# 7_Segment_Display_Peripheral.net
KiCad netlist of a schematic drawn in EAGLE
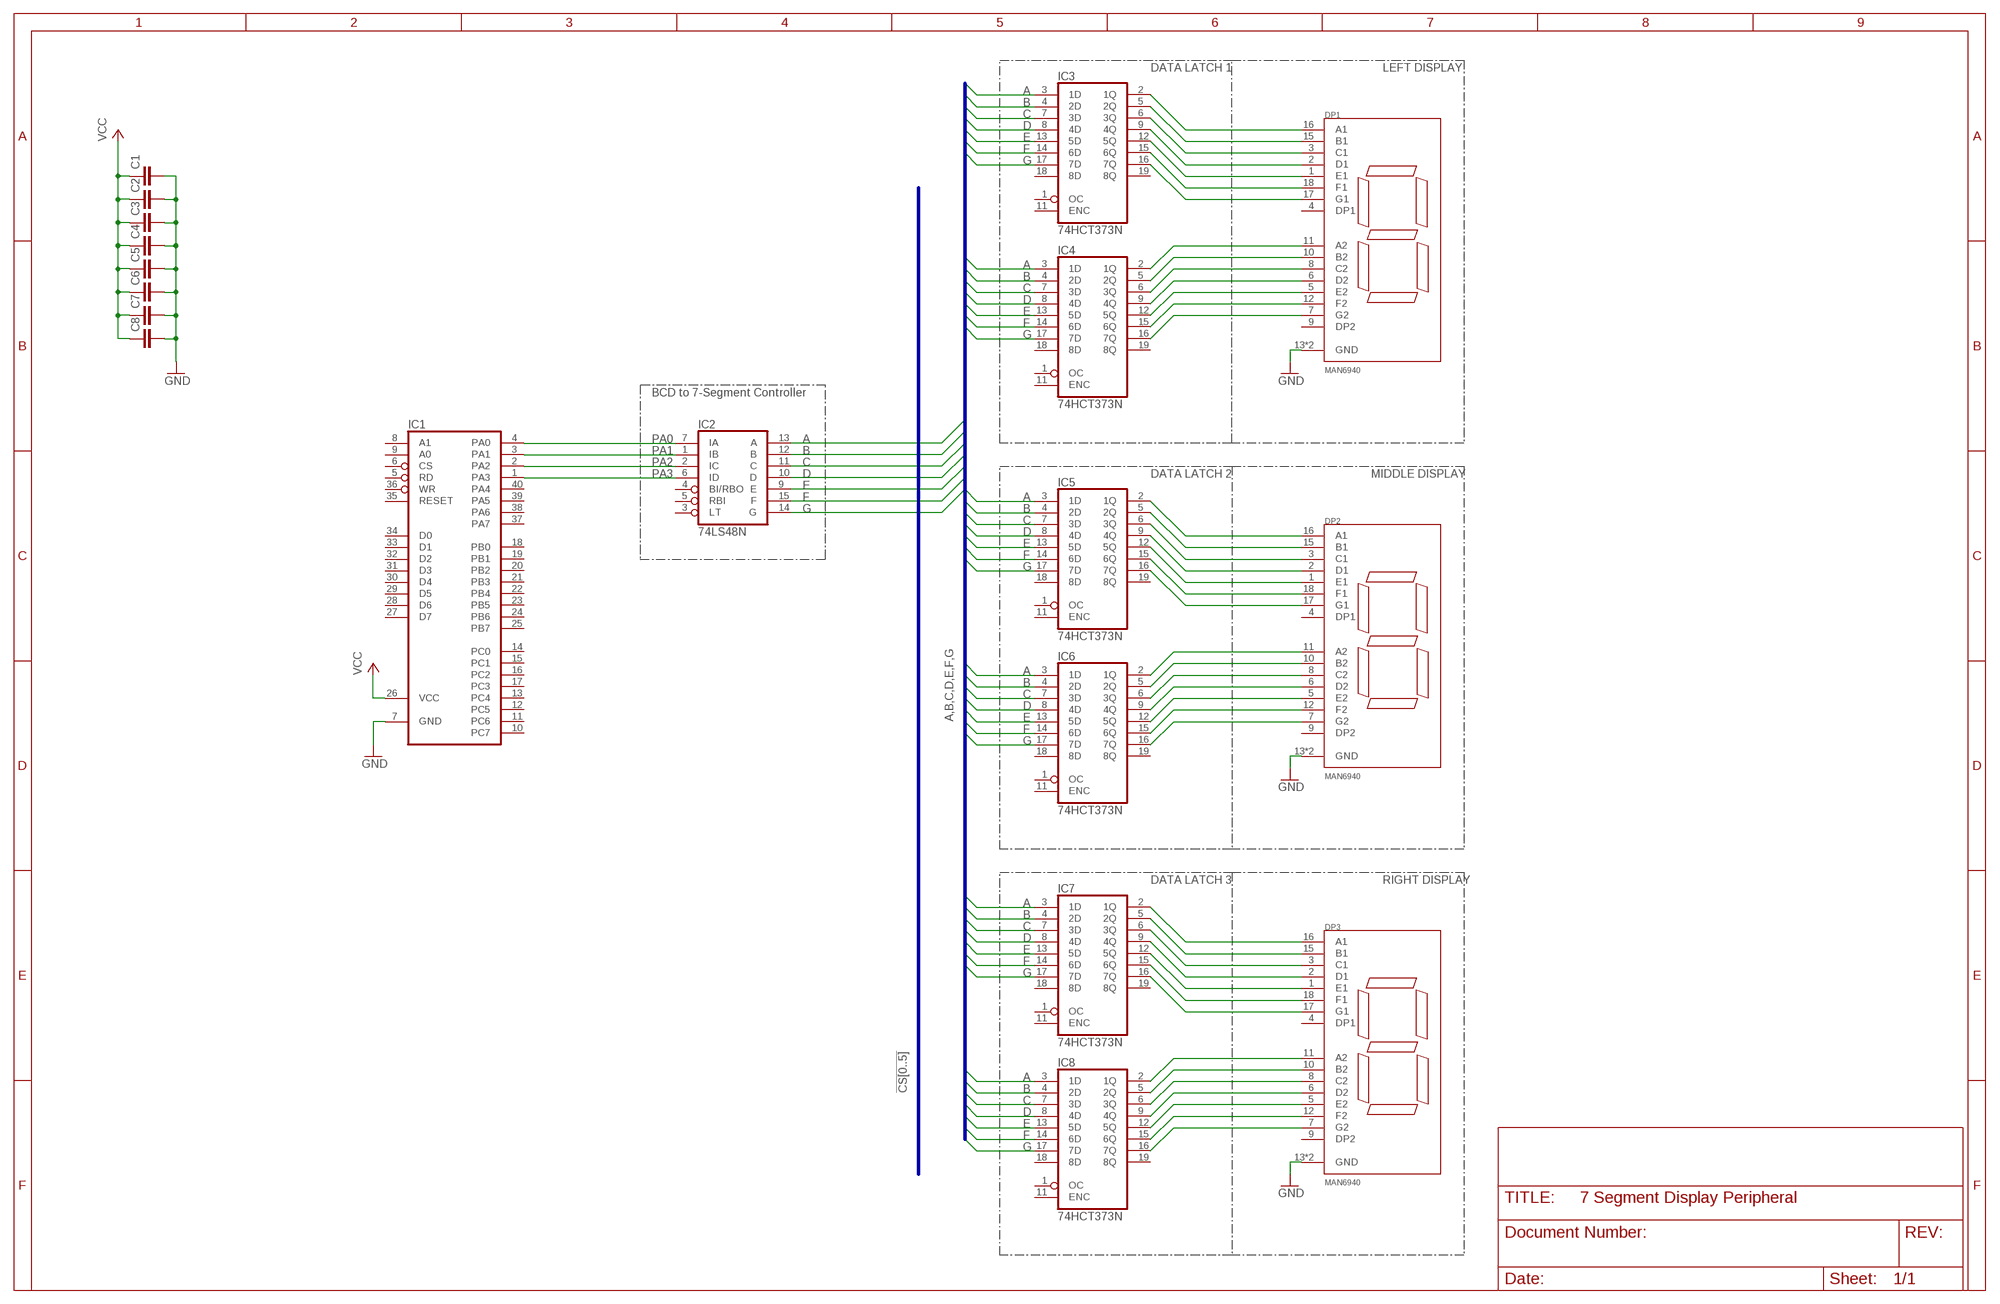
[diagram p0: schematic, sheet 1]

(export (version "E")
  (design (tool "Eeschema 10.0.6"))
  (components
    (comp (ref "C1")
      (value "C-EU050-024X044")
      (footprint "eagle-import:C050-024X044")
      (libsource (lib "eagle-import") (part "C-EU050-024X044"))
    )
    (comp (ref "C2")
      (value "C-EU050-024X044")
      (footprint "eagle-import:C050-024X044")
      (libsource (lib "eagle-import") (part "C-EU050-024X044"))
    )
    (comp (ref "C3")
      (value "C-EU050-024X044")
      (footprint "eagle-import:C050-024X044")
      (libsource (lib "eagle-import") (part "C-EU050-024X044"))
    )
    (comp (ref "C4")
      (value "C-EU050-024X044")
      (footprint "eagle-import:C050-024X044")
      (libsource (lib "eagle-import") (part "C-EU050-024X044"))
    )
    (comp (ref "C5")
      (value "C-EU050-024X044")
      (footprint "eagle-import:C050-024X044")
      (libsource (lib "eagle-import") (part "C-EU050-024X044"))
    )
    (comp (ref "C6")
      (value "C-EU050-024X044")
      (footprint "eagle-import:C050-024X044")
      (libsource (lib "eagle-import") (part "C-EU050-024X044"))
    )
    (comp (ref "C7")
      (value "C-EU050-024X044")
      (footprint "eagle-import:C050-024X044")
      (libsource (lib "eagle-import") (part "C-EU050-024X044"))
    )
    (comp (ref "C8")
      (value "C-EU050-024X044")
      (footprint "eagle-import:C050-024X044")
      (libsource (lib "eagle-import") (part "C-EU050-024X044"))
    )
    (comp (ref "DP1")
      (value "MAN6940")
      (footprint "eagle-import:MAN6940")
      (libsource (lib "eagle-import") (part "MAN6940"))
    )
    (comp (ref "DP2")
      (value "MAN6940")
      (footprint "eagle-import:MAN6940")
      (libsource (lib "eagle-import") (part "MAN6940"))
    )
    (comp (ref "DP3")
      (value "MAN6940")
      (footprint "eagle-import:MAN6940")
      (libsource (lib "eagle-import") (part "MAN6940"))
    )
    (comp (ref "IC1")
      (value "82C55A")
      (footprint "eagle-import:DIL40")
      (fields (field (name "MF") "INTERSIL") (field (name "MPN") "IP82C55AZ"))
      (libsource (lib "eagle-import") (part "82C55A"))
    )
    (comp (ref "IC2")
      (value "74LS48N")
      (footprint "eagle-import:DIL16")
      (libsource (lib "eagle-import") (part "7448NLS"))
    )
    (comp (ref "IC3")
      (value "74HCT373N")
      (footprint "eagle-import:DIL20")
      (libsource (lib "eagle-import") (part "74373NHCT"))
    )
    (comp (ref "IC4")
      (value "74HCT373N")
      (footprint "eagle-import:DIL20")
      (libsource (lib "eagle-import") (part "74373NHCT"))
    )
    (comp (ref "IC5")
      (value "74HCT373N")
      (footprint "eagle-import:DIL20")
      (libsource (lib "eagle-import") (part "74373NHCT"))
    )
    (comp (ref "IC6")
      (value "74HCT373N")
      (footprint "eagle-import:DIL20")
      (libsource (lib "eagle-import") (part "74373NHCT"))
    )
    (comp (ref "IC7")
      (value "74HCT373N")
      (footprint "eagle-import:DIL20")
      (libsource (lib "eagle-import") (part "74373NHCT"))
    )
    (comp (ref "IC8")
      (value "74HCT373N")
      (footprint "eagle-import:DIL20")
      (libsource (lib "eagle-import") (part "74373NHCT"))
    )
  )
  (nets
    (net (code "7") (name "/A") (class "Default")
      (node (ref "IC2") (pin "13") (pinfunction "A_13") (pintype "output"))
      (node (ref "IC3") (pin "3") (pinfunction "1D_3") (pintype "input"))
      (node (ref "IC4") (pin "3") (pinfunction "1D_3") (pintype "input"))
      (node (ref "IC5") (pin "3") (pinfunction "1D_3") (pintype "input"))
      (node (ref "IC6") (pin "3") (pinfunction "1D_3") (pintype "input"))
      (node (ref "IC7") (pin "3") (pinfunction "1D_3") (pintype "input"))
      (node (ref "IC8") (pin "3") (pinfunction "1D_3") (pintype "input"))
    )
    (net (code "8") (name "/B") (class "Default")
      (node (ref "IC2") (pin "12") (pinfunction "B_12") (pintype "output"))
      (node (ref "IC3") (pin "4") (pinfunction "2D_4") (pintype "input"))
      (node (ref "IC4") (pin "4") (pinfunction "2D_4") (pintype "input"))
      (node (ref "IC5") (pin "4") (pinfunction "2D_4") (pintype "input"))
      (node (ref "IC6") (pin "4") (pinfunction "2D_4") (pintype "input"))
      (node (ref "IC7") (pin "4") (pinfunction "2D_4") (pintype "input"))
      (node (ref "IC8") (pin "4") (pinfunction "2D_4") (pintype "input"))
    )
    (net (code "9") (name "/C") (class "Default")
      (node (ref "IC2") (pin "11") (pinfunction "C_11") (pintype "output"))
      (node (ref "IC3") (pin "7") (pinfunction "3D_7") (pintype "input"))
      (node (ref "IC4") (pin "7") (pinfunction "3D_7") (pintype "input"))
      (node (ref "IC5") (pin "7") (pinfunction "3D_7") (pintype "input"))
      (node (ref "IC6") (pin "7") (pinfunction "3D_7") (pintype "input"))
      (node (ref "IC7") (pin "7") (pinfunction "3D_7") (pintype "input"))
      (node (ref "IC8") (pin "7") (pinfunction "3D_7") (pintype "input"))
    )
    (net (code "10") (name "/D") (class "Default")
      (node (ref "IC2") (pin "10") (pinfunction "D_10") (pintype "output"))
      (node (ref "IC3") (pin "8") (pinfunction "4D_8") (pintype "input"))
      (node (ref "IC4") (pin "8") (pinfunction "4D_8") (pintype "input"))
      (node (ref "IC5") (pin "8") (pinfunction "4D_8") (pintype "input"))
      (node (ref "IC6") (pin "8") (pinfunction "4D_8") (pintype "input"))
      (node (ref "IC7") (pin "8") (pinfunction "4D_8") (pintype "input"))
      (node (ref "IC8") (pin "8") (pinfunction "4D_8") (pintype "input"))
    )
    (net (code "11") (name "/E") (class "Default")
      (node (ref "IC2") (pin "9") (pinfunction "E_9") (pintype "output"))
      (node (ref "IC3") (pin "13") (pinfunction "5D_13") (pintype "input"))
      (node (ref "IC4") (pin "13") (pinfunction "5D_13") (pintype "input"))
      (node (ref "IC5") (pin "13") (pinfunction "5D_13") (pintype "input"))
      (node (ref "IC6") (pin "13") (pinfunction "5D_13") (pintype "input"))
      (node (ref "IC7") (pin "13") (pinfunction "5D_13") (pintype "input"))
      (node (ref "IC8") (pin "13") (pinfunction "5D_13") (pintype "input"))
    )
    (net (code "12") (name "/F") (class "Default")
      (node (ref "IC2") (pin "15") (pinfunction "F_15") (pintype "output"))
      (node (ref "IC3") (pin "14") (pinfunction "6D_14") (pintype "input"))
      (node (ref "IC4") (pin "14") (pinfunction "6D_14") (pintype "input"))
      (node (ref "IC5") (pin "14") (pinfunction "6D_14") (pintype "input"))
      (node (ref "IC6") (pin "14") (pinfunction "6D_14") (pintype "input"))
      (node (ref "IC7") (pin "14") (pinfunction "6D_14") (pintype "input"))
      (node (ref "IC8") (pin "14") (pinfunction "6D_14") (pintype "input"))
    )
    (net (code "13") (name "/G") (class "Default")
      (node (ref "IC2") (pin "14") (pinfunction "G_14") (pintype "output"))
      (node (ref "IC3") (pin "17") (pinfunction "7D_17") (pintype "input"))
      (node (ref "IC4") (pin "17") (pinfunction "7D_17") (pintype "input"))
      (node (ref "IC5") (pin "17") (pinfunction "7D_17") (pintype "input"))
      (node (ref "IC6") (pin "17") (pinfunction "7D_17") (pintype "input"))
      (node (ref "IC7") (pin "17") (pinfunction "7D_17") (pintype "input"))
      (node (ref "IC8") (pin "17") (pinfunction "7D_17") (pintype "input"))
    )
    (net (code "14") (name "/PA0") (class "Default")
      (node (ref "IC1") (pin "4") (pinfunction "PA0_4") (pintype "bidirectional"))
      (node (ref "IC2") (pin "7") (pinfunction "IA_7") (pintype "input"))
    )
    (net (code "15") (name "/PA1") (class "Default")
      (node (ref "IC1") (pin "3") (pinfunction "PA1_3") (pintype "bidirectional"))
      (node (ref "IC2") (pin "1") (pinfunction "IB_1") (pintype "input"))
    )
    (net (code "16") (name "/PA2") (class "Default")
      (node (ref "IC1") (pin "2") (pinfunction "PA2_2") (pintype "bidirectional"))
      (node (ref "IC2") (pin "2") (pinfunction "IC_2") (pintype "input"))
    )
    (net (code "17") (name "/PA3") (class "Default")
      (node (ref "IC1") (pin "1") (pinfunction "PA3_1") (pintype "bidirectional"))
      (node (ref "IC2") (pin "6") (pinfunction "ID_6") (pintype "input"))
    )
    (net (code "20") (name "GND") (class "Default")
      (node (ref "C1") (pin "2") (pinfunction "2_2") (pintype "passive"))
      (node (ref "C2") (pin "2") (pinfunction "2_2") (pintype "passive"))
      (node (ref "C3") (pin "2") (pinfunction "2_2") (pintype "passive"))
      (node (ref "C4") (pin "2") (pinfunction "2_2") (pintype "passive"))
      (node (ref "C5") (pin "2") (pinfunction "2_2") (pintype "passive"))
      (node (ref "C6") (pin "2") (pinfunction "2_2") (pintype "passive"))
      (node (ref "C7") (pin "2") (pinfunction "2_2") (pintype "passive"))
      (node (ref "C8") (pin "2") (pinfunction "2_2") (pintype "passive"))
      (node (ref "DP1") (pin "13") (pinfunction "GND_13") (pintype "power_in"))
      (node (ref "DP1") (pin "14") (pinfunction "GND_14") (pintype "power_in"))
      (node (ref "DP2") (pin "13") (pinfunction "GND_13") (pintype "power_in"))
      (node (ref "DP2") (pin "14") (pinfunction "GND_14") (pintype "power_in"))
      (node (ref "DP3") (pin "13") (pinfunction "GND_13") (pintype "power_in"))
      (node (ref "DP3") (pin "14") (pinfunction "GND_14") (pintype "power_in"))
      (node (ref "IC1") (pin "7") (pinfunction "GND_7") (pintype "power_in"))
    )
    (net (code "21") (name "Net-(DP1-A1)") (class "Default")
      (node (ref "DP1") (pin "16") (pinfunction "A1_16") (pintype "input"))
      (node (ref "IC3") (pin "2") (pinfunction "1Q_2") (pintype "tri_state"))
    )
    (net (code "22") (name "Net-(DP1-A2)") (class "Default")
      (node (ref "DP1") (pin "11") (pinfunction "A2_11") (pintype "input"))
      (node (ref "IC4") (pin "2") (pinfunction "1Q_2") (pintype "tri_state"))
    )
    (net (code "23") (name "Net-(DP1-B1)") (class "Default")
      (node (ref "DP1") (pin "15") (pinfunction "B1_15") (pintype "input"))
      (node (ref "IC3") (pin "5") (pinfunction "2Q_5") (pintype "tri_state"))
    )
    (net (code "24") (name "Net-(DP1-B2)") (class "Default")
      (node (ref "DP1") (pin "10") (pinfunction "B2_10") (pintype "input"))
      (node (ref "IC4") (pin "5") (pinfunction "2Q_5") (pintype "tri_state"))
    )
    (net (code "25") (name "Net-(DP1-C1)") (class "Default")
      (node (ref "DP1") (pin "3") (pinfunction "C1_3") (pintype "input"))
      (node (ref "IC3") (pin "6") (pinfunction "3Q_6") (pintype "tri_state"))
    )
    (net (code "26") (name "Net-(DP1-C2)") (class "Default")
      (node (ref "DP1") (pin "8") (pinfunction "C2_8") (pintype "input"))
      (node (ref "IC4") (pin "6") (pinfunction "3Q_6") (pintype "tri_state"))
    )
    (net (code "27") (name "Net-(DP1-D1)") (class "Default")
      (node (ref "DP1") (pin "2") (pinfunction "D1_2") (pintype "input"))
      (node (ref "IC3") (pin "9") (pinfunction "4Q_9") (pintype "tri_state"))
    )
    (net (code "28") (name "Net-(DP1-D2)") (class "Default")
      (node (ref "DP1") (pin "6") (pinfunction "D2_6") (pintype "input"))
      (node (ref "IC4") (pin "9") (pinfunction "4Q_9") (pintype "tri_state"))
    )
    (net (code "29") (name "Net-(DP1-E1)") (class "Default")
      (node (ref "DP1") (pin "1") (pinfunction "E1_1") (pintype "input"))
      (node (ref "IC3") (pin "12") (pinfunction "5Q_12") (pintype "tri_state"))
    )
    (net (code "30") (name "Net-(DP1-E2)") (class "Default")
      (node (ref "DP1") (pin "5") (pinfunction "E2_5") (pintype "input"))
      (node (ref "IC4") (pin "12") (pinfunction "5Q_12") (pintype "tri_state"))
    )
    (net (code "31") (name "Net-(DP1-F1)") (class "Default")
      (node (ref "DP1") (pin "18") (pinfunction "F1_18") (pintype "input"))
      (node (ref "IC3") (pin "15") (pinfunction "6Q_15") (pintype "tri_state"))
    )
    (net (code "32") (name "Net-(DP1-F2)") (class "Default")
      (node (ref "DP1") (pin "12") (pinfunction "F2_12") (pintype "input"))
      (node (ref "IC4") (pin "15") (pinfunction "6Q_15") (pintype "tri_state"))
    )
    (net (code "33") (name "Net-(DP1-G1)") (class "Default")
      (node (ref "DP1") (pin "17") (pinfunction "G1_17") (pintype "input"))
      (node (ref "IC3") (pin "16") (pinfunction "7Q_16") (pintype "tri_state"))
    )
    (net (code "34") (name "Net-(DP1-G2)") (class "Default")
      (node (ref "DP1") (pin "7") (pinfunction "G2_7") (pintype "input"))
      (node (ref "IC4") (pin "16") (pinfunction "7Q_16") (pintype "tri_state"))
    )
    (net (code "35") (name "Net-(DP2-A1)") (class "Default")
      (node (ref "DP2") (pin "16") (pinfunction "A1_16") (pintype "input"))
      (node (ref "IC5") (pin "2") (pinfunction "1Q_2") (pintype "tri_state"))
    )
    (net (code "36") (name "Net-(DP2-A2)") (class "Default")
      (node (ref "DP2") (pin "11") (pinfunction "A2_11") (pintype "input"))
      (node (ref "IC6") (pin "2") (pinfunction "1Q_2") (pintype "tri_state"))
    )
    (net (code "37") (name "Net-(DP2-B1)") (class "Default")
      (node (ref "DP2") (pin "15") (pinfunction "B1_15") (pintype "input"))
      (node (ref "IC5") (pin "5") (pinfunction "2Q_5") (pintype "tri_state"))
    )
    (net (code "38") (name "Net-(DP2-B2)") (class "Default")
      (node (ref "DP2") (pin "10") (pinfunction "B2_10") (pintype "input"))
      (node (ref "IC6") (pin "5") (pinfunction "2Q_5") (pintype "tri_state"))
    )
    (net (code "39") (name "Net-(DP2-C1)") (class "Default")
      (node (ref "DP2") (pin "3") (pinfunction "C1_3") (pintype "input"))
      (node (ref "IC5") (pin "6") (pinfunction "3Q_6") (pintype "tri_state"))
    )
    (net (code "40") (name "Net-(DP2-C2)") (class "Default")
      (node (ref "DP2") (pin "8") (pinfunction "C2_8") (pintype "input"))
      (node (ref "IC6") (pin "6") (pinfunction "3Q_6") (pintype "tri_state"))
    )
    (net (code "41") (name "Net-(DP2-D1)") (class "Default")
      (node (ref "DP2") (pin "2") (pinfunction "D1_2") (pintype "input"))
      (node (ref "IC5") (pin "9") (pinfunction "4Q_9") (pintype "tri_state"))
    )
    (net (code "42") (name "Net-(DP2-D2)") (class "Default")
      (node (ref "DP2") (pin "6") (pinfunction "D2_6") (pintype "input"))
      (node (ref "IC6") (pin "9") (pinfunction "4Q_9") (pintype "tri_state"))
    )
    (net (code "43") (name "Net-(DP2-E1)") (class "Default")
      (node (ref "DP2") (pin "1") (pinfunction "E1_1") (pintype "input"))
      (node (ref "IC5") (pin "12") (pinfunction "5Q_12") (pintype "tri_state"))
    )
    (net (code "44") (name "Net-(DP2-E2)") (class "Default")
      (node (ref "DP2") (pin "5") (pinfunction "E2_5") (pintype "input"))
      (node (ref "IC6") (pin "12") (pinfunction "5Q_12") (pintype "tri_state"))
    )
    (net (code "45") (name "Net-(DP2-F1)") (class "Default")
      (node (ref "DP2") (pin "18") (pinfunction "F1_18") (pintype "input"))
      (node (ref "IC5") (pin "15") (pinfunction "6Q_15") (pintype "tri_state"))
    )
    (net (code "46") (name "Net-(DP2-F2)") (class "Default")
      (node (ref "DP2") (pin "12") (pinfunction "F2_12") (pintype "input"))
      (node (ref "IC6") (pin "15") (pinfunction "6Q_15") (pintype "tri_state"))
    )
    (net (code "47") (name "Net-(DP2-G1)") (class "Default")
      (node (ref "DP2") (pin "17") (pinfunction "G1_17") (pintype "input"))
      (node (ref "IC5") (pin "16") (pinfunction "7Q_16") (pintype "tri_state"))
    )
    (net (code "48") (name "Net-(DP2-G2)") (class "Default")
      (node (ref "DP2") (pin "7") (pinfunction "G2_7") (pintype "input"))
      (node (ref "IC6") (pin "16") (pinfunction "7Q_16") (pintype "tri_state"))
    )
    (net (code "49") (name "Net-(DP3-A1)") (class "Default")
      (node (ref "DP3") (pin "16") (pinfunction "A1_16") (pintype "input"))
      (node (ref "IC7") (pin "2") (pinfunction "1Q_2") (pintype "tri_state"))
    )
    (net (code "50") (name "Net-(DP3-A2)") (class "Default")
      (node (ref "DP3") (pin "11") (pinfunction "A2_11") (pintype "input"))
      (node (ref "IC8") (pin "2") (pinfunction "1Q_2") (pintype "tri_state"))
    )
    (net (code "51") (name "Net-(DP3-B1)") (class "Default")
      (node (ref "DP3") (pin "15") (pinfunction "B1_15") (pintype "input"))
      (node (ref "IC7") (pin "5") (pinfunction "2Q_5") (pintype "tri_state"))
    )
    (net (code "52") (name "Net-(DP3-B2)") (class "Default")
      (node (ref "DP3") (pin "10") (pinfunction "B2_10") (pintype "input"))
      (node (ref "IC8") (pin "5") (pinfunction "2Q_5") (pintype "tri_state"))
    )
    (net (code "53") (name "Net-(DP3-C1)") (class "Default")
      (node (ref "DP3") (pin "3") (pinfunction "C1_3") (pintype "input"))
      (node (ref "IC7") (pin "6") (pinfunction "3Q_6") (pintype "tri_state"))
    )
    (net (code "54") (name "Net-(DP3-C2)") (class "Default")
      (node (ref "DP3") (pin "8") (pinfunction "C2_8") (pintype "input"))
      (node (ref "IC8") (pin "6") (pinfunction "3Q_6") (pintype "tri_state"))
    )
    (net (code "55") (name "Net-(DP3-D1)") (class "Default")
      (node (ref "DP3") (pin "2") (pinfunction "D1_2") (pintype "input"))
      (node (ref "IC7") (pin "9") (pinfunction "4Q_9") (pintype "tri_state"))
    )
    (net (code "56") (name "Net-(DP3-D2)") (class "Default")
      (node (ref "DP3") (pin "6") (pinfunction "D2_6") (pintype "input"))
      (node (ref "IC8") (pin "9") (pinfunction "4Q_9") (pintype "tri_state"))
    )
    (net (code "57") (name "Net-(DP3-E1)") (class "Default")
      (node (ref "DP3") (pin "1") (pinfunction "E1_1") (pintype "input"))
      (node (ref "IC7") (pin "12") (pinfunction "5Q_12") (pintype "tri_state"))
    )
    (net (code "58") (name "Net-(DP3-E2)") (class "Default")
      (node (ref "DP3") (pin "5") (pinfunction "E2_5") (pintype "input"))
      (node (ref "IC8") (pin "12") (pinfunction "5Q_12") (pintype "tri_state"))
    )
    (net (code "59") (name "Net-(DP3-F1)") (class "Default")
      (node (ref "DP3") (pin "18") (pinfunction "F1_18") (pintype "input"))
      (node (ref "IC7") (pin "15") (pinfunction "6Q_15") (pintype "tri_state"))
    )
    (net (code "60") (name "Net-(DP3-F2)") (class "Default")
      (node (ref "DP3") (pin "12") (pinfunction "F2_12") (pintype "input"))
      (node (ref "IC8") (pin "15") (pinfunction "6Q_15") (pintype "tri_state"))
    )
    (net (code "61") (name "Net-(DP3-G1)") (class "Default")
      (node (ref "DP3") (pin "17") (pinfunction "G1_17") (pintype "input"))
      (node (ref "IC7") (pin "16") (pinfunction "7Q_16") (pintype "tri_state"))
    )
    (net (code "62") (name "Net-(DP3-G2)") (class "Default")
      (node (ref "DP3") (pin "7") (pinfunction "G2_7") (pintype "input"))
      (node (ref "IC8") (pin "16") (pinfunction "7Q_16") (pintype "tri_state"))
    )
    (net (code "63") (name "VCC") (class "Default")
      (node (ref "C1") (pin "1") (pinfunction "1_1") (pintype "passive"))
      (node (ref "C2") (pin "1") (pinfunction "1_1") (pintype "passive"))
      (node (ref "C3") (pin "1") (pinfunction "1_1") (pintype "passive"))
      (node (ref "C4") (pin "1") (pinfunction "1_1") (pintype "passive"))
      (node (ref "C5") (pin "1") (pinfunction "1_1") (pintype "passive"))
      (node (ref "C6") (pin "1") (pinfunction "1_1") (pintype "passive"))
      (node (ref "C7") (pin "1") (pinfunction "1_1") (pintype "passive"))
      (node (ref "C8") (pin "1") (pinfunction "1_1") (pintype "passive"))
      (node (ref "IC1") (pin "26") (pinfunction "VCC_26") (pintype "power_in"))
    )
    (net (code "64") (name "unconnected-(DP1-DP1-Pad4)") (class "Default")
      (node (ref "DP1") (pin "4") (pinfunction "DP1_4") (pintype "input"))
    )
    (net (code "65") (name "unconnected-(DP1-DP2-Pad9)") (class "Default")
      (node (ref "DP1") (pin "9") (pinfunction "DP2_9") (pintype "input"))
    )
    (net (code "66") (name "unconnected-(DP2-DP1-Pad4)") (class "Default")
      (node (ref "DP2") (pin "4") (pinfunction "DP1_4") (pintype "input"))
    )
    (net (code "67") (name "unconnected-(DP2-DP2-Pad9)") (class "Default")
      (node (ref "DP2") (pin "9") (pinfunction "DP2_9") (pintype "input"))
    )
    (net (code "68") (name "unconnected-(DP3-DP1-Pad4)") (class "Default")
      (node (ref "DP3") (pin "4") (pinfunction "DP1_4") (pintype "input"))
    )
    (net (code "69") (name "unconnected-(DP3-DP2-Pad9)") (class "Default")
      (node (ref "DP3") (pin "9") (pinfunction "DP2_9") (pintype "input"))
    )
    (net (code "70") (name "unconnected-(IC1-A0-Pad9)") (class "Default")
      (node (ref "IC1") (pin "9") (pinfunction "A0_9") (pintype "input"))
    )
    (net (code "71") (name "unconnected-(IC1-A1-Pad8)") (class "Default")
      (node (ref "IC1") (pin "8") (pinfunction "A1_8") (pintype "input"))
    )
    (net (code "72") (name "unconnected-(IC1-CS-Pad6)") (class "Default")
      (node (ref "IC1") (pin "6") (pinfunction "CS_6") (pintype "input"))
    )
    (net (code "73") (name "unconnected-(IC1-D0-Pad34)") (class "Default")
      (node (ref "IC1") (pin "34") (pinfunction "D0_34") (pintype "bidirectional"))
    )
    (net (code "74") (name "unconnected-(IC1-D1-Pad33)") (class "Default")
      (node (ref "IC1") (pin "33") (pinfunction "D1_33") (pintype "bidirectional"))
    )
    (net (code "75") (name "unconnected-(IC1-D2-Pad32)") (class "Default")
      (node (ref "IC1") (pin "32") (pinfunction "D2_32") (pintype "bidirectional"))
    )
    (net (code "76") (name "unconnected-(IC1-D3-Pad31)") (class "Default")
      (node (ref "IC1") (pin "31") (pinfunction "D3_31") (pintype "bidirectional"))
    )
    (net (code "77") (name "unconnected-(IC1-D4-Pad30)") (class "Default")
      (node (ref "IC1") (pin "30") (pinfunction "D4_30") (pintype "bidirectional"))
    )
    (net (code "78") (name "unconnected-(IC1-D5-Pad29)") (class "Default")
      (node (ref "IC1") (pin "29") (pinfunction "D5_29") (pintype "bidirectional"))
    )
    (net (code "79") (name "unconnected-(IC1-D6-Pad28)") (class "Default")
      (node (ref "IC1") (pin "28") (pinfunction "D6_28") (pintype "bidirectional"))
    )
    (net (code "80") (name "unconnected-(IC1-D7-Pad27)") (class "Default")
      (node (ref "IC1") (pin "27") (pinfunction "D7_27") (pintype "bidirectional"))
    )
    (net (code "81") (name "unconnected-(IC1-PA4-Pad40)") (class "Default")
      (node (ref "IC1") (pin "40") (pinfunction "PA4_40") (pintype "bidirectional"))
    )
    (net (code "82") (name "unconnected-(IC1-PA5-Pad39)") (class "Default")
      (node (ref "IC1") (pin "39") (pinfunction "PA5_39") (pintype "bidirectional"))
    )
    (net (code "83") (name "unconnected-(IC1-PA6-Pad38)") (class "Default")
      (node (ref "IC1") (pin "38") (pinfunction "PA6_38") (pintype "bidirectional"))
    )
    (net (code "84") (name "unconnected-(IC1-PA7-Pad37)") (class "Default")
      (node (ref "IC1") (pin "37") (pinfunction "PA7_37") (pintype "bidirectional"))
    )
    (net (code "85") (name "unconnected-(IC1-PB0-Pad18)") (class "Default")
      (node (ref "IC1") (pin "18") (pinfunction "PB0_18") (pintype "bidirectional"))
    )
    (net (code "86") (name "unconnected-(IC1-PB1-Pad19)") (class "Default")
      (node (ref "IC1") (pin "19") (pinfunction "PB1_19") (pintype "bidirectional"))
    )
    (net (code "87") (name "unconnected-(IC1-PB2-Pad20)") (class "Default")
      (node (ref "IC1") (pin "20") (pinfunction "PB2_20") (pintype "bidirectional"))
    )
    (net (code "88") (name "unconnected-(IC1-PB3-Pad21)") (class "Default")
      (node (ref "IC1") (pin "21") (pinfunction "PB3_21") (pintype "bidirectional"))
    )
    (net (code "89") (name "unconnected-(IC1-PB4-Pad22)") (class "Default")
      (node (ref "IC1") (pin "22") (pinfunction "PB4_22") (pintype "bidirectional"))
    )
    (net (code "90") (name "unconnected-(IC1-PB5-Pad23)") (class "Default")
      (node (ref "IC1") (pin "23") (pinfunction "PB5_23") (pintype "bidirectional"))
    )
    (net (code "91") (name "unconnected-(IC1-PB6-Pad24)") (class "Default")
      (node (ref "IC1") (pin "24") (pinfunction "PB6_24") (pintype "bidirectional"))
    )
    (net (code "92") (name "unconnected-(IC1-PB7-Pad25)") (class "Default")
      (node (ref "IC1") (pin "25") (pinfunction "PB7_25") (pintype "bidirectional"))
    )
    (net (code "93") (name "unconnected-(IC1-PC0-Pad14)") (class "Default")
      (node (ref "IC1") (pin "14") (pinfunction "PC0_14") (pintype "bidirectional"))
    )
    (net (code "94") (name "unconnected-(IC1-PC1-Pad15)") (class "Default")
      (node (ref "IC1") (pin "15") (pinfunction "PC1_15") (pintype "bidirectional"))
    )
    (net (code "95") (name "unconnected-(IC1-PC2-Pad16)") (class "Default")
      (node (ref "IC1") (pin "16") (pinfunction "PC2_16") (pintype "bidirectional"))
    )
    (net (code "96") (name "unconnected-(IC1-PC3-Pad17)") (class "Default")
      (node (ref "IC1") (pin "17") (pinfunction "PC3_17") (pintype "bidirectional"))
    )
    (net (code "97") (name "unconnected-(IC1-PC4-Pad13)") (class "Default")
      (node (ref "IC1") (pin "13") (pinfunction "PC4_13") (pintype "bidirectional"))
    )
    (net (code "98") (name "unconnected-(IC1-PC5-Pad12)") (class "Default")
      (node (ref "IC1") (pin "12") (pinfunction "PC5_12") (pintype "bidirectional"))
    )
    (net (code "99") (name "unconnected-(IC1-PC6-Pad11)") (class "Default")
      (node (ref "IC1") (pin "11") (pinfunction "PC6_11") (pintype "bidirectional"))
    )
    (net (code "100") (name "unconnected-(IC1-PC7-Pad10)") (class "Default")
      (node (ref "IC1") (pin "10") (pinfunction "PC7_10") (pintype "bidirectional"))
    )
    (net (code "101") (name "unconnected-(IC1-RD-Pad5)") (class "Default")
      (node (ref "IC1") (pin "5") (pinfunction "RD_5") (pintype "input"))
    )
    (net (code "102") (name "unconnected-(IC1-RESET-Pad35)") (class "Default")
      (node (ref "IC1") (pin "35") (pinfunction "RESET_35") (pintype "input"))
    )
    (net (code "103") (name "unconnected-(IC1-WR-Pad36)") (class "Default")
      (node (ref "IC1") (pin "36") (pinfunction "WR_36") (pintype "input"))
    )
    (net (code "104") (name "unconnected-(IC2A-BI{slash}RBO-Pad4)") (class "Default")
      (node (ref "IC2") (pin "4") (pinfunction "BI/RBO_4") (pintype "input"))
    )
    (net (code "105") (name "unconnected-(IC2A-LT-Pad3)") (class "Default")
      (node (ref "IC2") (pin "3") (pinfunction "LT_3") (pintype "input"))
    )
    (net (code "106") (name "unconnected-(IC2A-RBI-Pad5)") (class "Default")
      (node (ref "IC2") (pin "5") (pinfunction "RBI_5") (pintype "input"))
    )
    (net (code "107") (name "unconnected-(IC3A-8D-Pad18)") (class "Default")
      (node (ref "IC3") (pin "18") (pinfunction "8D_18") (pintype "input"))
    )
    (net (code "108") (name "unconnected-(IC3A-8Q-Pad19)") (class "Default")
      (node (ref "IC3") (pin "19") (pinfunction "8Q_19") (pintype "tri_state"))
    )
    (net (code "109") (name "unconnected-(IC3A-ENC-Pad11)") (class "Default")
      (node (ref "IC3") (pin "11") (pinfunction "ENC_11") (pintype "input"))
    )
    (net (code "110") (name "unconnected-(IC3A-OC-Pad1)") (class "Default")
      (node (ref "IC3") (pin "1") (pinfunction "OC_1") (pintype "input"))
    )
    (net (code "111") (name "unconnected-(IC4A-8D-Pad18)") (class "Default")
      (node (ref "IC4") (pin "18") (pinfunction "8D_18") (pintype "input"))
    )
    (net (code "112") (name "unconnected-(IC4A-8Q-Pad19)") (class "Default")
      (node (ref "IC4") (pin "19") (pinfunction "8Q_19") (pintype "tri_state"))
    )
    (net (code "113") (name "unconnected-(IC4A-ENC-Pad11)") (class "Default")
      (node (ref "IC4") (pin "11") (pinfunction "ENC_11") (pintype "input"))
    )
    (net (code "114") (name "unconnected-(IC4A-OC-Pad1)") (class "Default")
      (node (ref "IC4") (pin "1") (pinfunction "OC_1") (pintype "input"))
    )
    (net (code "115") (name "unconnected-(IC5A-8D-Pad18)") (class "Default")
      (node (ref "IC5") (pin "18") (pinfunction "8D_18") (pintype "input"))
    )
    (net (code "116") (name "unconnected-(IC5A-8Q-Pad19)") (class "Default")
      (node (ref "IC5") (pin "19") (pinfunction "8Q_19") (pintype "tri_state"))
    )
    (net (code "117") (name "unconnected-(IC5A-ENC-Pad11)") (class "Default")
      (node (ref "IC5") (pin "11") (pinfunction "ENC_11") (pintype "input"))
    )
    (net (code "118") (name "unconnected-(IC5A-OC-Pad1)") (class "Default")
      (node (ref "IC5") (pin "1") (pinfunction "OC_1") (pintype "input"))
    )
    (net (code "119") (name "unconnected-(IC6A-8D-Pad18)") (class "Default")
      (node (ref "IC6") (pin "18") (pinfunction "8D_18") (pintype "input"))
    )
    (net (code "120") (name "unconnected-(IC6A-8Q-Pad19)") (class "Default")
      (node (ref "IC6") (pin "19") (pinfunction "8Q_19") (pintype "tri_state"))
    )
    (net (code "121") (name "unconnected-(IC6A-ENC-Pad11)") (class "Default")
      (node (ref "IC6") (pin "11") (pinfunction "ENC_11") (pintype "input"))
    )
    (net (code "122") (name "unconnected-(IC6A-OC-Pad1)") (class "Default")
      (node (ref "IC6") (pin "1") (pinfunction "OC_1") (pintype "input"))
    )
    (net (code "123") (name "unconnected-(IC7A-8D-Pad18)") (class "Default")
      (node (ref "IC7") (pin "18") (pinfunction "8D_18") (pintype "input"))
    )
    (net (code "124") (name "unconnected-(IC7A-8Q-Pad19)") (class "Default")
      (node (ref "IC7") (pin "19") (pinfunction "8Q_19") (pintype "tri_state"))
    )
    (net (code "125") (name "unconnected-(IC7A-ENC-Pad11)") (class "Default")
      (node (ref "IC7") (pin "11") (pinfunction "ENC_11") (pintype "input"))
    )
    (net (code "126") (name "unconnected-(IC7A-OC-Pad1)") (class "Default")
      (node (ref "IC7") (pin "1") (pinfunction "OC_1") (pintype "input"))
    )
    (net (code "127") (name "unconnected-(IC8A-8D-Pad18)") (class "Default")
      (node (ref "IC8") (pin "18") (pinfunction "8D_18") (pintype "input"))
    )
    (net (code "128") (name "unconnected-(IC8A-8Q-Pad19)") (class "Default")
      (node (ref "IC8") (pin "19") (pinfunction "8Q_19") (pintype "tri_state"))
    )
    (net (code "129") (name "unconnected-(IC8A-ENC-Pad11)") (class "Default")
      (node (ref "IC8") (pin "11") (pinfunction "ENC_11") (pintype "input"))
    )
    (net (code "130") (name "unconnected-(IC8A-OC-Pad1)") (class "Default")
      (node (ref "IC8") (pin "1") (pinfunction "OC_1") (pintype "input"))
    )
  )
)
